# pjvs_mux_v1.net
KiCad netlist of a schematic drawn in EAGLE
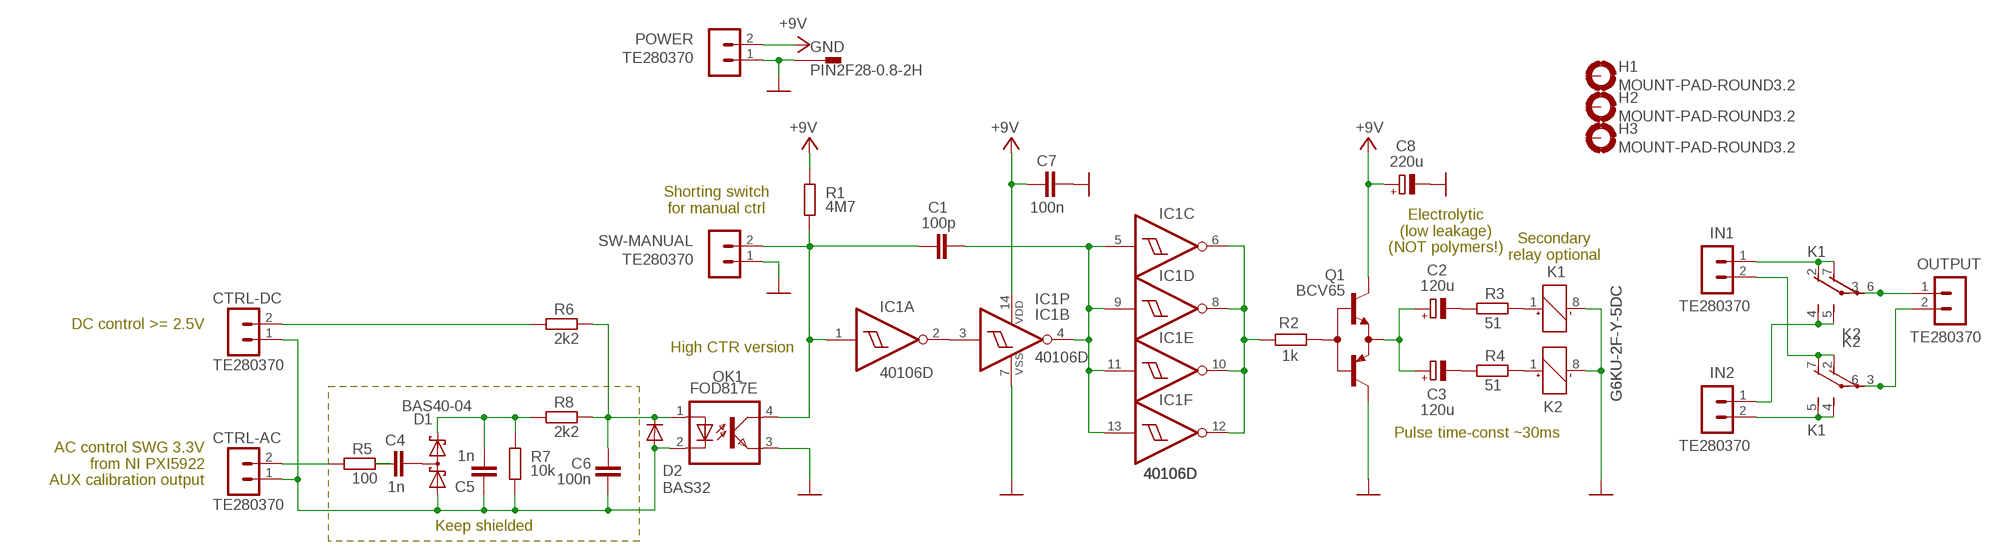
[diagram p0: schematic, sheet 1]

(export (version "E")
  (design (tool "Eeschema 10.0.6"))
  (components
    (comp (ref "C1")
      (value "100p")
      (footprint "eagle-import:C025-024X044")
      (libsource (lib "eagle-import") (part "C-EU025-024X044"))
    )
    (comp (ref "C2")
      (value "120u")
      (footprint "eagle-import:E2,5-7")
      (libsource (lib "eagle-import") (part "CPOL-EUE2.5-7"))
    )
    (comp (ref "C3")
      (value "120u")
      (footprint "eagle-import:E2,5-7")
      (libsource (lib "eagle-import") (part "CPOL-EUE2.5-7"))
    )
    (comp (ref "C4")
      (value "1n")
      (footprint "eagle-import:C0805K")
      (libsource (lib "eagle-import") (part "C-EUC0805K"))
    )
    (comp (ref "C5")
      (value "1n")
      (footprint "eagle-import:C0805K")
      (libsource (lib "eagle-import") (part "C-EUC0805K"))
    )
    (comp (ref "C6")
      (value "100n")
      (footprint "eagle-import:C0805K")
      (libsource (lib "eagle-import") (part "C-EUC0805K"))
    )
    (comp (ref "C7")
      (value "100n")
      (footprint "eagle-import:C0805K")
      (libsource (lib "eagle-import") (part "C-EUC0805K"))
    )
    (comp (ref "C8")
      (value "220u")
      (footprint "eagle-import:E3,5-8")
      (libsource (lib "eagle-import") (part "CPOL-EUE3.5-8"))
    )
    (comp (ref "CTRL-AC")
      (value "TE280370")
      (footprint "eagle-import:TE280370")
      (libsource (lib "eagle-import") (part "TE280370"))
    )
    (comp (ref "CTRL-DC")
      (value "TE280370")
      (footprint "eagle-import:TE280370")
      (libsource (lib "eagle-import") (part "TE280370"))
    )
    (comp (ref "D1")
      (value "BAS40-04")
      (footprint "eagle-import:SOT23")
      (libsource (lib "eagle-import") (part "BAS40-04"))
    )
    (comp (ref "D2")
      (value "BAS32")
      (footprint "eagle-import:SOD80C")
      (libsource (lib "eagle-import") (part "BAS32"))
    )
    (comp (ref "GND")
      (value "PIN2F28-0.8-2H")
      (footprint "eagle-import:F28-0.8-2H")
      (libsource (lib "eagle-import") (part "PIN2F28-0.8-2H"))
    )
    (comp (ref "H1")
      (value "MOUNT-PAD-ROUND3.2")
      (footprint "eagle-import:3,2-PAD")
      (libsource (lib "eagle-import") (part "MOUNT-PAD-ROUND3.2"))
    )
    (comp (ref "H2")
      (value "MOUNT-PAD-ROUND3.2")
      (footprint "eagle-import:3,2-PAD")
      (libsource (lib "eagle-import") (part "MOUNT-PAD-ROUND3.2"))
    )
    (comp (ref "H3")
      (value "MOUNT-PAD-ROUND3.2")
      (footprint "eagle-import:3,2-PAD")
      (libsource (lib "eagle-import") (part "MOUNT-PAD-ROUND3.2"))
    )
    (comp (ref "IC1")
      (value "40106D")
      (footprint "eagle-import:SO14")
      (libsource (lib "eagle-import") (part "40106D"))
    )
    (comp (ref "IN1")
      (value "TE280370")
      (footprint "eagle-import:TE280370")
      (libsource (lib "eagle-import") (part "TE280370"))
    )
    (comp (ref "IN2")
      (value "TE280370")
      (footprint "eagle-import:TE280370")
      (libsource (lib "eagle-import") (part "TE280370"))
    )
    (comp (ref "K1")
      (value "G6KU-2F-Y-5DC")
      (footprint "eagle-import:G6KU-2F-Y")
      (fields (field (name "MF") "OMRON COMPONENTS USA") (field (name "MPN") "G6KU-2F-Y DC3"))
      (libsource (lib "eagle-import") (part "G6KU-2F-Y"))
    )
    (comp (ref "K2")
      (value "G6KU-2F-Y-5DC")
      (footprint "eagle-import:G6KU-2F-Y")
      (fields (field (name "MF") "OMRON COMPONENTS USA") (field (name "MPN") "G6KU-2F-Y DC3"))
      (libsource (lib "eagle-import") (part "G6KU-2F-Y"))
    )
    (comp (ref "OK1")
      (value "FOD817E")
      (footprint "eagle-import:DIL04")
      (fields (field (name "MPN") "PC817X4J000F"))
      (libsource (lib "eagle-import") (part "PC817"))
    )
    (comp (ref "OUTPUT")
      (value "TE280370")
      (footprint "eagle-import:TE280370")
      (libsource (lib "eagle-import") (part "TE280370"))
    )
    (comp (ref "POWER")
      (value "TE280370")
      (footprint "eagle-import:TE280370")
      (libsource (lib "eagle-import") (part "TE280370"))
    )
    (comp (ref "Q1")
      (value "BCV65")
      (footprint "eagle-import:SOT143")
      (libsource (lib "eagle-import") (part "BCV62"))
    )
    (comp (ref "R1")
      (value "4M7")
      (footprint "eagle-import:0207_2V")
      (libsource (lib "eagle-import") (part "R-EU_0207/2V"))
    )
    (comp (ref "R2")
      (value "1k")
      (footprint "eagle-import:R0805")
      (libsource (lib "eagle-import") (part "R-EU_R0805"))
    )
    (comp (ref "R3")
      (value "51")
      (footprint "eagle-import:R0805")
      (libsource (lib "eagle-import") (part "R-EU_R0805"))
    )
    (comp (ref "R4")
      (value "51")
      (footprint "eagle-import:R0805")
      (libsource (lib "eagle-import") (part "R-EU_R0805"))
    )
    (comp (ref "R5")
      (value "100")
      (footprint "eagle-import:R0805")
      (libsource (lib "eagle-import") (part "R-EU_R0805"))
    )
    (comp (ref "R6")
      (value "2k2")
      (footprint "eagle-import:R0805")
      (libsource (lib "eagle-import") (part "R-EU_R0805"))
    )
    (comp (ref "R7")
      (value "10k")
      (footprint "eagle-import:R0805")
      (libsource (lib "eagle-import") (part "R-EU_R0805"))
    )
    (comp (ref "R8")
      (value "2k2")
      (footprint "eagle-import:R0805")
      (libsource (lib "eagle-import") (part "R-EU_R0805"))
    )
    (comp (ref "SW-MANUAL")
      (value "TE280370")
      (footprint "eagle-import:TE280370")
      (libsource (lib "eagle-import") (part "TE280370"))
    )
  )
  (nets
    (net (code "1") (name "+9V") (class "Default")
      (node (ref "C7") (pin "1") (pinfunction "1_1") (pintype "passive"))
      (node (ref "C8") (pin "+") (pinfunction "+_+") (pintype "passive"))
      (node (ref "IC1") (pin "14") (pinfunction "VDD_14") (pintype "power_in"))
      (node (ref "POWER") (pin "2") (pinfunction "2_2") (pintype "passive"))
      (node (ref "Q1") (pin "1") (pinfunction "C1_1") (pintype "passive"))
      (node (ref "R1") (pin "2") (pinfunction "2_2") (pintype "passive"))
    )
    (net (code "2") (name "GND") (class "Default")
      (node (ref "C7") (pin "2") (pinfunction "2_2") (pintype "passive"))
      (node (ref "C8") (pin "-") (pinfunction "-_-") (pintype "passive"))
      (node (ref "GND") (pin "P$1") (pinfunction "1_P$1") (pintype "passive"))
      (node (ref "GND") (pin "P$2") (pinfunction "1_P$2") (pintype "passive"))
      (node (ref "IC1") (pin "7") (pinfunction "VSS_7") (pintype "power_in"))
      (node (ref "K1") (pin "8") (pinfunction "-_8") (pintype "passive"))
      (node (ref "K2") (pin "8") (pinfunction "-_8") (pintype "passive"))
      (node (ref "OK1") (pin "3") (pinfunction "EMIT_3") (pintype "passive"))
      (node (ref "POWER") (pin "1") (pinfunction "1_1") (pintype "passive"))
      (node (ref "Q1") (pin "3") (pinfunction "C2_3") (pintype "passive"))
      (node (ref "SW-MANUAL") (pin "1") (pinfunction "1_1") (pintype "passive"))
    )
    (net (code "3") (name "Net-(C2-Pad-)") (class "Default")
      (node (ref "C2") (pin "-") (pinfunction "-_-") (pintype "passive"))
      (node (ref "R3") (pin "1") (pinfunction "1_1") (pintype "passive"))
    )
    (net (code "4") (name "Net-(C3-Pad-)") (class "Default")
      (node (ref "C3") (pin "-") (pinfunction "-_-") (pintype "passive"))
      (node (ref "R4") (pin "1") (pinfunction "1_1") (pintype "passive"))
    )
    (net (code "5") (name "Net-(C4-Pad1)") (class "Default")
      (node (ref "C4") (pin "1") (pinfunction "1_1") (pintype "passive"))
      (node (ref "R5") (pin "2") (pinfunction "2_2") (pintype "passive"))
    )
    (net (code "6") (name "Net-(CTRL-AC-Pad2)") (class "Default")
      (node (ref "CTRL-AC") (pin "2") (pinfunction "2_2") (pintype "passive"))
      (node (ref "R5") (pin "1") (pinfunction "1_1") (pintype "passive"))
    )
    (net (code "7") (name "Net-(CTRL-DC-Pad2)") (class "Default")
      (node (ref "CTRL-DC") (pin "2") (pinfunction "2_2") (pintype "passive"))
      (node (ref "R6") (pin "1") (pinfunction "1_1") (pintype "passive"))
    )
    (net (code "8") (name "Net-(D1-A1)") (class "Default")
      (node (ref "C5") (pin "1") (pinfunction "1_1") (pintype "passive"))
      (node (ref "C6") (pin "1") (pinfunction "1_1") (pintype "passive"))
      (node (ref "CTRL-AC") (pin "1") (pinfunction "1_1") (pintype "passive"))
      (node (ref "CTRL-DC") (pin "1") (pinfunction "1_1") (pintype "passive"))
      (node (ref "D1") (pin "1") (pinfunction "A1_1") (pintype "passive"))
      (node (ref "D2") (pin "A") (pinfunction "A_A") (pintype "passive"))
      (node (ref "OK1") (pin "2") (pinfunction "C_2") (pintype "passive"))
      (node (ref "R7") (pin "1") (pinfunction "1_1") (pintype "passive"))
    )
    (net (code "9") (name "Net-(D1-C1A2)") (class "Default")
      (node (ref "C4") (pin "2") (pinfunction "2_2") (pintype "passive"))
      (node (ref "D1") (pin "3") (pinfunction "C1A2_3") (pintype "passive"))
    )
    (net (code "10") (name "Net-(D1-C2)") (class "Default")
      (node (ref "C5") (pin "2") (pinfunction "2_2") (pintype "passive"))
      (node (ref "D1") (pin "2") (pinfunction "C2_2") (pintype "passive"))
      (node (ref "R7") (pin "2") (pinfunction "2_2") (pintype "passive"))
      (node (ref "R8") (pin "1") (pinfunction "1_1") (pintype "passive"))
    )
    (net (code "11") (name "Net-(IC1A-I)") (class "Default")
      (node (ref "C1") (pin "1") (pinfunction "1_1") (pintype "passive"))
      (node (ref "IC1") (pin "1") (pinfunction "I_1") (pintype "input"))
      (node (ref "OK1") (pin "4") (pinfunction "COL_4") (pintype "passive"))
      (node (ref "R1") (pin "1") (pinfunction "1_1") (pintype "passive"))
      (node (ref "SW-MANUAL") (pin "2") (pinfunction "2_2") (pintype "passive"))
    )
    (net (code "12") (name "Net-(IC1A-O)") (class "Default")
      (node (ref "IC1") (pin "2") (pinfunction "O_2") (pintype "output"))
      (node (ref "IC1") (pin "3") (pinfunction "I_3") (pintype "input"))
    )
    (net (code "13") (name "Net-(IC1B-O)") (class "Default")
      (node (ref "C1") (pin "2") (pinfunction "2_2") (pintype "passive"))
      (node (ref "IC1") (pin "11") (pinfunction "I_11") (pintype "input"))
      (node (ref "IC1") (pin "13") (pinfunction "I_13") (pintype "input"))
      (node (ref "IC1") (pin "4") (pinfunction "O_4") (pintype "output"))
      (node (ref "IC1") (pin "5") (pinfunction "I_5") (pintype "input"))
      (node (ref "IC1") (pin "9") (pinfunction "I_9") (pintype "input"))
    )
    (net (code "14") (name "Net-(IC1C-O)") (class "Default")
      (node (ref "IC1") (pin "10") (pinfunction "O_10") (pintype "output"))
      (node (ref "IC1") (pin "12") (pinfunction "O_12") (pintype "output"))
      (node (ref "IC1") (pin "6") (pinfunction "O_6") (pintype "output"))
      (node (ref "IC1") (pin "8") (pinfunction "O_8") (pintype "output"))
      (node (ref "R2") (pin "2") (pinfunction "2_2") (pintype "passive"))
    )
    (net (code "15") (name "Net-(K1A-+)") (class "Default")
      (node (ref "K1") (pin "1") (pinfunction "+_1") (pintype "passive"))
      (node (ref "R3") (pin "2") (pinfunction "2_2") (pintype "passive"))
    )
    (net (code "16") (name "Net-(K1B-O)") (class "Default")
      (node (ref "IN1") (pin "1") (pinfunction "1_1") (pintype "passive"))
      (node (ref "K1") (pin "2") (pinfunction "O_2") (pintype "passive"))
      (node (ref "K2") (pin "7") (pinfunction "O_7") (pintype "passive"))
    )
    (net (code "17") (name "Net-(K1B-P)") (class "Default")
      (node (ref "K1") (pin "3") (pinfunction "P_3") (pintype "passive"))
      (node (ref "K2") (pin "6") (pinfunction "P_6") (pintype "passive"))
      (node (ref "OUTPUT") (pin "1") (pinfunction "1_1") (pintype "passive"))
    )
    (net (code "18") (name "Net-(K1B-S)") (class "Default")
      (node (ref "IN2") (pin "1") (pinfunction "1_1") (pintype "passive"))
      (node (ref "K1") (pin "4") (pinfunction "S_4") (pintype "passive"))
      (node (ref "K2") (pin "5") (pinfunction "S_5") (pintype "passive"))
    )
    (net (code "19") (name "Net-(K1C-O)") (class "Default")
      (node (ref "IN1") (pin "2") (pinfunction "2_2") (pintype "passive"))
      (node (ref "K1") (pin "7") (pinfunction "O_7") (pintype "passive"))
      (node (ref "K2") (pin "2") (pinfunction "O_2") (pintype "passive"))
    )
    (net (code "20") (name "Net-(K1C-P)") (class "Default")
      (node (ref "K1") (pin "6") (pinfunction "P_6") (pintype "passive"))
      (node (ref "K2") (pin "3") (pinfunction "P_3") (pintype "passive"))
      (node (ref "OUTPUT") (pin "2") (pinfunction "2_2") (pintype "passive"))
    )
    (net (code "21") (name "Net-(K1C-S)") (class "Default")
      (node (ref "IN2") (pin "2") (pinfunction "2_2") (pintype "passive"))
      (node (ref "K1") (pin "5") (pinfunction "S_5") (pintype "passive"))
      (node (ref "K2") (pin "4") (pinfunction "S_4") (pintype "passive"))
    )
    (net (code "22") (name "Net-(K2A-+)") (class "Default")
      (node (ref "K2") (pin "1") (pinfunction "+_1") (pintype "passive"))
      (node (ref "R4") (pin "2") (pinfunction "2_2") (pintype "passive"))
    )
    (net (code "23") (name "Net-(OK1-A)") (class "Default")
      (node (ref "C6") (pin "2") (pinfunction "2_2") (pintype "passive"))
      (node (ref "D2") (pin "C") (pinfunction "C_C") (pintype "passive"))
      (node (ref "OK1") (pin "1") (pinfunction "A_1") (pintype "passive"))
      (node (ref "R6") (pin "2") (pinfunction "2_2") (pintype "passive"))
      (node (ref "R8") (pin "2") (pinfunction "2_2") (pintype "passive"))
    )
    (net (code "24") (name "Net-(Q1-B)") (class "Default")
      (node (ref "Q1") (pin "2") (pinfunction "B_2") (pintype "passive"))
      (node (ref "R2") (pin "1") (pinfunction "1_1") (pintype "passive"))
    )
    (net (code "25") (name "Net-(Q1-E)") (class "Default")
      (node (ref "C2") (pin "+") (pinfunction "+_+") (pintype "passive"))
      (node (ref "C3") (pin "+") (pinfunction "+_+") (pintype "passive"))
      (node (ref "Q1") (pin "4") (pinfunction "E_4") (pintype "passive"))
    )
    (net (code "26") (name "unconnected-(H1-MOUNT-PadB3,2)") (class "Default")
      (node (ref "H1") (pin "B3,2") (pinfunction "MOUNT_B3,2") (pintype "passive"))
    )
    (net (code "27") (name "unconnected-(H2-MOUNT-PadB3,2)") (class "Default")
      (node (ref "H2") (pin "B3,2") (pinfunction "MOUNT_B3,2") (pintype "passive"))
    )
    (net (code "28") (name "unconnected-(H3-MOUNT-PadB3,2)") (class "Default")
      (node (ref "H3") (pin "B3,2") (pinfunction "MOUNT_B3,2") (pintype "passive"))
    )
  )
)
